# mux_lowside-V1_00.net
KiCad netlist of a schematic drawn in Altium Designer
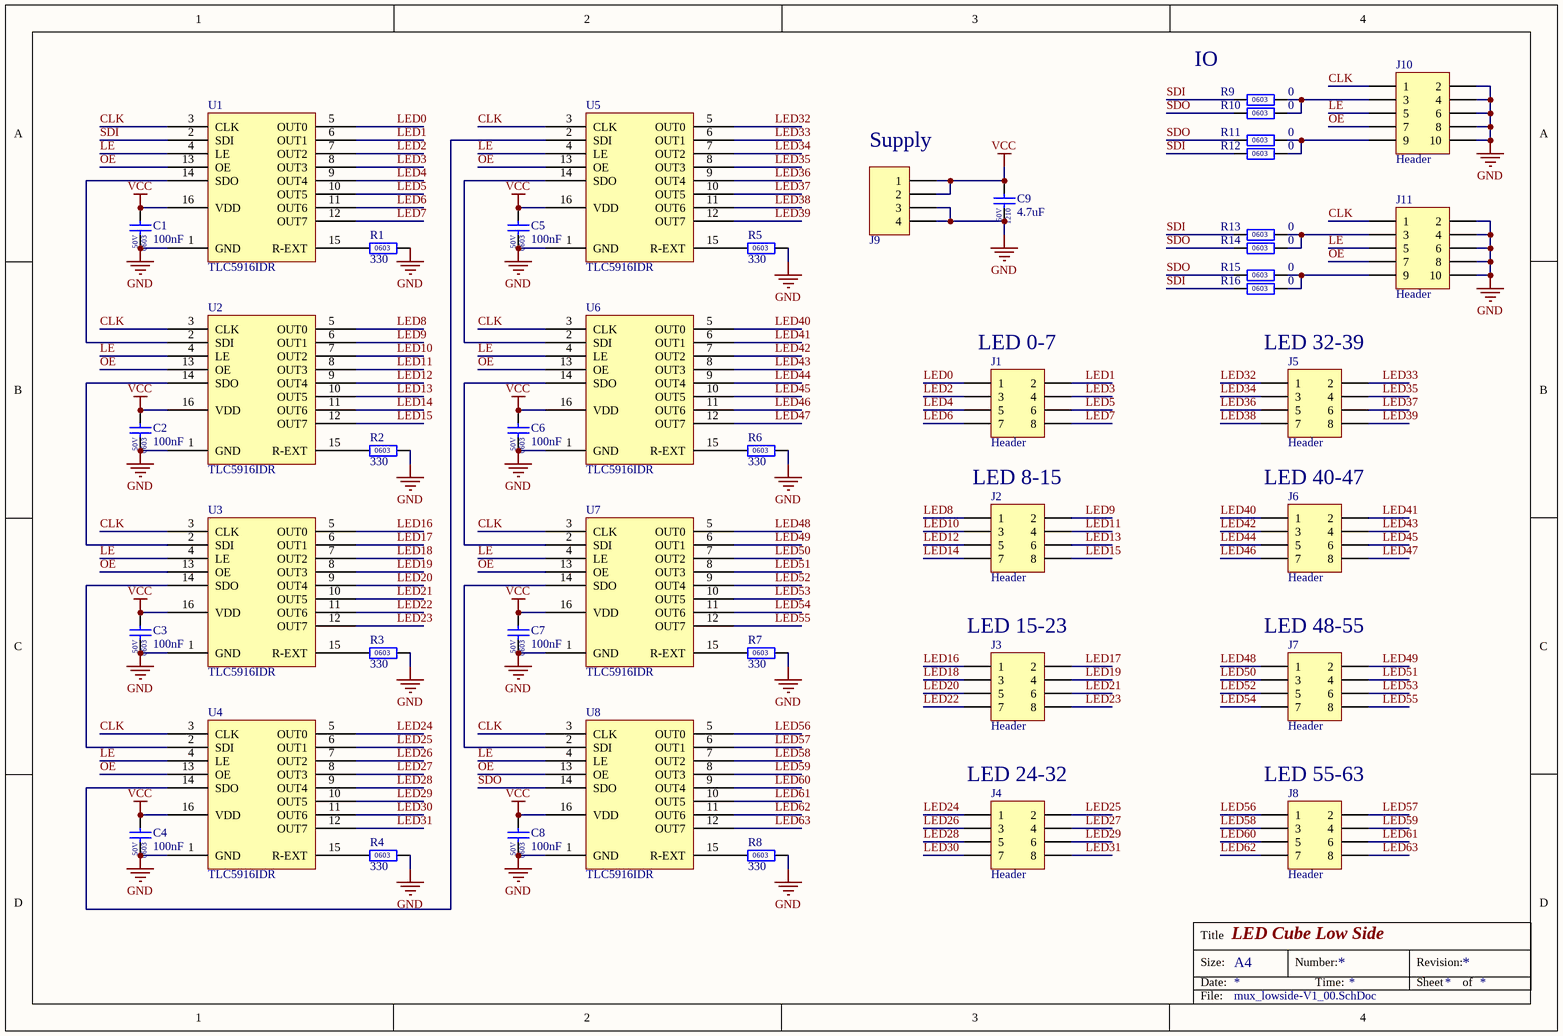
[diagram p0: mux_lowside-V1_00.SchDoc]

(export (version "E")
  (design (tool "Eeschema 10.0.6"))
  (components
    (comp (ref "C1")
      (value "Capacitor")
      (footprint "CAPC1608X10M_SILK")
      (description "CAP nF100   50V 0603 X7R 10%")
      (fields
        (field (name "MAX. VOLTAGE") "50V")
        (field (name "CAPACITY") "100nF")
        (field (name "PACKAGE") "0603")
        (field (name "PART NUMBER") "11026540")
        (field (name "TOLERANCE") "10%")
      )
      (libsource (lib "parts") (part "Capacitor"))
    )
    (comp (ref "C2")
      (value "Capacitor")
      (footprint "CAPC1608X10M_SILK")
      (description "CAP nF100   50V 0603 X7R 10%")
      (fields
        (field (name "MAX. VOLTAGE") "50V")
        (field (name "CAPACITY") "100nF")
        (field (name "PACKAGE") "0603")
        (field (name "PART NUMBER") "11026540")
        (field (name "TOLERANCE") "10%")
      )
      (libsource (lib "parts") (part "Capacitor"))
    )
    (comp (ref "C3")
      (value "Capacitor")
      (footprint "CAPC1608X10M_SILK")
      (description "CAP nF100   50V 0603 X7R 10%")
      (fields
        (field (name "MAX. VOLTAGE") "50V")
        (field (name "CAPACITY") "100nF")
        (field (name "PACKAGE") "0603")
        (field (name "PART NUMBER") "11026540")
        (field (name "TOLERANCE") "10%")
      )
      (libsource (lib "parts") (part "Capacitor"))
    )
    (comp (ref "C4")
      (value "Capacitor")
      (footprint "CAPC1608X10M_SILK")
      (description "CAP nF100   50V 0603 X7R 10%")
      (fields
        (field (name "MAX. VOLTAGE") "50V")
        (field (name "CAPACITY") "100nF")
        (field (name "PACKAGE") "0603")
        (field (name "PART NUMBER") "11026540")
        (field (name "TOLERANCE") "10%")
      )
      (libsource (lib "parts") (part "Capacitor"))
    )
    (comp (ref "C5")
      (value "Capacitor")
      (footprint "CAPC1608X10M_SILK")
      (description "CAP nF100   50V 0603 X7R 10%")
      (fields
        (field (name "MAX. VOLTAGE") "50V")
        (field (name "CAPACITY") "100nF")
        (field (name "PACKAGE") "0603")
        (field (name "PART NUMBER") "11026540")
        (field (name "TOLERANCE") "10%")
      )
      (libsource (lib "parts") (part "Capacitor"))
    )
    (comp (ref "C6")
      (value "Capacitor")
      (footprint "CAPC1608X10M_SILK")
      (description "CAP nF100   50V 0603 X7R 10%")
      (fields
        (field (name "MAX. VOLTAGE") "50V")
        (field (name "CAPACITY") "100nF")
        (field (name "PACKAGE") "0603")
        (field (name "PART NUMBER") "11026540")
        (field (name "TOLERANCE") "10%")
      )
      (libsource (lib "parts") (part "Capacitor"))
    )
    (comp (ref "C7")
      (value "Capacitor")
      (footprint "CAPC1608X10M_SILK")
      (description "CAP nF100   50V 0603 X7R 10%")
      (fields
        (field (name "MAX. VOLTAGE") "50V")
        (field (name "CAPACITY") "100nF")
        (field (name "PACKAGE") "0603")
        (field (name "PART NUMBER") "11026540")
        (field (name "TOLERANCE") "10%")
      )
      (libsource (lib "parts") (part "Capacitor"))
    )
    (comp (ref "C8")
      (value "Capacitor")
      (footprint "CAPC1608X10M_SILK")
      (description "CAP nF100   50V 0603 X7R 10%")
      (fields
        (field (name "MAX. VOLTAGE") "50V")
        (field (name "CAPACITY") "100nF")
        (field (name "PACKAGE") "0603")
        (field (name "PART NUMBER") "11026540")
        (field (name "TOLERANCE") "10%")
      )
      (libsource (lib "parts") (part "Capacitor"))
    )
    (comp (ref "C9")
      (value "Capacitor")
      (footprint "CAPC3225X17M_SILK")
      (description "CAP uF  4.7 50V 1210 X7R 10%")
      (fields
        (field (name "MAX. VOLTAGE") "50V")
        (field (name "CAPACITY") "4.7uF")
        (field (name "PACKAGE") "1210")
        (field (name "PART NUMBER") "10159411")
        (field (name "TOLERANCE") "10%")
      )
      (libsource (lib "parts") (part "Capacitor"))
    )
    (comp (ref "J1")
      (value "Header")
      (footprint "61200821621")
      (description "Box Header Male THT 2.54mm straight 8pos")
      (fields (field (name "PART NUMBER") "61200821621") (field (name "MANUFACTURER") "Wuerth"))
      (libsource (lib "parts") (part "Conn_02x04"))
    )
    (comp (ref "J2")
      (value "Header")
      (footprint "61200821621")
      (description "Box Header Male THT 2.54mm straight 8pos")
      (fields (field (name "PART NUMBER") "61200821621") (field (name "MANUFACTURER") "Wuerth"))
      (libsource (lib "parts") (part "Conn_02x04"))
    )
    (comp (ref "J3")
      (value "Header")
      (footprint "61200821621")
      (description "Box Header Male THT 2.54mm straight 8pos")
      (fields (field (name "PART NUMBER") "61200821621") (field (name "MANUFACTURER") "Wuerth"))
      (libsource (lib "parts") (part "Conn_02x04"))
    )
    (comp (ref "J4")
      (value "Header")
      (footprint "61200821621")
      (description "Box Header Male THT 2.54mm straight 8pos")
      (fields (field (name "PART NUMBER") "61200821621") (field (name "MANUFACTURER") "Wuerth"))
      (libsource (lib "parts") (part "Conn_02x04"))
    )
    (comp (ref "J5")
      (value "Header")
      (footprint "61200821621")
      (description "Box Header Male THT 2.54mm straight 8pos")
      (fields (field (name "PART NUMBER") "61200821621") (field (name "MANUFACTURER") "Wuerth"))
      (libsource (lib "parts") (part "Conn_02x04"))
    )
    (comp (ref "J6")
      (value "Header")
      (footprint "61200821621")
      (description "Box Header Male THT 2.54mm straight 8pos")
      (fields (field (name "PART NUMBER") "61200821621") (field (name "MANUFACTURER") "Wuerth"))
      (libsource (lib "parts") (part "Conn_02x04"))
    )
    (comp (ref "J7")
      (value "Header")
      (footprint "61200821621")
      (description "Box Header Male THT 2.54mm straight 8pos")
      (fields (field (name "PART NUMBER") "61200821621") (field (name "MANUFACTURER") "Wuerth"))
      (libsource (lib "parts") (part "Conn_02x04"))
    )
    (comp (ref "J8")
      (value "Header")
      (footprint "61200821621")
      (description "Box Header Male THT 2.54mm straight 8pos")
      (fields (field (name "PART NUMBER") "61200821621") (field (name "MANUFACTURER") "Wuerth"))
      (libsource (lib "parts") (part "Conn_02x04"))
    )
    (comp (ref "J9")
      (value "MSTBA 2,5/ 4-G-5,08")
      (footprint "1757268")
      (description "PCB Header, 2.54mm, angled, 4pol")
      (fields (field (name "MANUFACTURER") "Phoenix Contact"))
      (libsource (lib "parts") (part "Conn_01x04"))
    )
    (comp (ref "J10")
      (value "Header")
      (footprint "61201021721")
      (description "Box Header Male THT 2.54mm angled 10pos")
      (fields (field (name "PART NUMBER") "61201021721") (field (name "MANUFACTURER") "Wuerth"))
      (libsource (lib "parts") (part "Conn_02x05"))
    )
    (comp (ref "J11")
      (value "Header")
      (footprint "61201021721")
      (description "Box Header Male THT 2.54mm angled 10pos")
      (fields (field (name "PART NUMBER") "61201021721") (field (name "MANUFACTURER") "Wuerth"))
      (libsource (lib "parts") (part "Conn_02x05"))
    )
    (comp (ref "R1")
      (value "330")
      (footprint "RESC1608X06M_SILK")
      (description "Resistor 330 1% 0603")
      (fields
        (field (name "PACKAGE") "0603")
        (field (name "PART NUMBER") "RES_330_0603")
        (field (name "TOLERANCE") "1%")
      )
      (libsource (lib "parts") (part "resistor"))
    )
    (comp (ref "R2")
      (value "330")
      (footprint "RESC1608X06M_SILK")
      (description "Resistor 330 1% 0603")
      (fields
        (field (name "PACKAGE") "0603")
        (field (name "PART NUMBER") "RES_330_0603")
        (field (name "TOLERANCE") "1%")
      )
      (libsource (lib "parts") (part "resistor"))
    )
    (comp (ref "R3")
      (value "330")
      (footprint "RESC1608X06M_SILK")
      (description "Resistor 330 1% 0603")
      (fields
        (field (name "PACKAGE") "0603")
        (field (name "PART NUMBER") "RES_330_0603")
        (field (name "TOLERANCE") "1%")
      )
      (libsource (lib "parts") (part "resistor"))
    )
    (comp (ref "R4")
      (value "330")
      (footprint "RESC1608X06M_SILK")
      (description "Resistor 330 1% 0603")
      (fields
        (field (name "PACKAGE") "0603")
        (field (name "PART NUMBER") "RES_330_0603")
        (field (name "TOLERANCE") "1%")
      )
      (libsource (lib "parts") (part "resistor"))
    )
    (comp (ref "R5")
      (value "330")
      (footprint "RESC1608X06M_SILK")
      (description "Resistor 330 1% 0603")
      (fields
        (field (name "PACKAGE") "0603")
        (field (name "PART NUMBER") "RES_330_0603")
        (field (name "TOLERANCE") "1%")
      )
      (libsource (lib "parts") (part "resistor"))
    )
    (comp (ref "R6")
      (value "330")
      (footprint "RESC1608X06M_SILK")
      (description "Resistor 330 1% 0603")
      (fields
        (field (name "PACKAGE") "0603")
        (field (name "PART NUMBER") "RES_330_0603")
        (field (name "TOLERANCE") "1%")
      )
      (libsource (lib "parts") (part "resistor"))
    )
    (comp (ref "R7")
      (value "330")
      (footprint "RESC1608X06M_SILK")
      (description "Resistor 330 1% 0603")
      (fields
        (field (name "PACKAGE") "0603")
        (field (name "PART NUMBER") "RES_330_0603")
        (field (name "TOLERANCE") "1%")
      )
      (libsource (lib "parts") (part "resistor"))
    )
    (comp (ref "R8")
      (value "330")
      (footprint "RESC1608X06M_SILK")
      (description "Resistor 330 1% 0603")
      (fields
        (field (name "PACKAGE") "0603")
        (field (name "PART NUMBER") "RES_330_0603")
        (field (name "TOLERANCE") "1%")
      )
      (libsource (lib "parts") (part "resistor"))
    )
    (comp (ref "R9")
      (value "0")
      (footprint "RESC1608X06M_SILK")
      (description "Resistor 0 1% 0603")
      (fields
        (field (name "PACKAGE") "0603")
        (field (name "PART NUMBER") "RES_0_0603")
        (field (name "TOLERANCE") "1%")
      )
      (libsource (lib "parts") (part "resistor"))
    )
    (comp (ref "R10")
      (value "0")
      (footprint "RESC1608X06M_SILK")
      (description "Resistor 0 1% 0603")
      (fields
        (field (name "PACKAGE") "0603")
        (field (name "PART NUMBER") "RES_0_0603")
        (field (name "TOLERANCE") "1%")
      )
      (libsource (lib "parts") (part "resistor"))
    )
    (comp (ref "R11")
      (value "0")
      (footprint "RESC1608X06M_SILK")
      (description "Resistor 0 1% 0603")
      (fields
        (field (name "PACKAGE") "0603")
        (field (name "PART NUMBER") "RES_0_0603")
        (field (name "TOLERANCE") "1%")
      )
      (libsource (lib "parts") (part "resistor"))
    )
    (comp (ref "R12")
      (value "0")
      (footprint "RESC1608X06M_SILK")
      (description "Resistor 0 1% 0603")
      (fields
        (field (name "PACKAGE") "0603")
        (field (name "PART NUMBER") "RES_0_0603")
        (field (name "TOLERANCE") "1%")
      )
      (libsource (lib "parts") (part "resistor"))
    )
    (comp (ref "R13")
      (value "0")
      (footprint "RESC1608X06M_SILK")
      (description "Resistor 0 1% 0603")
      (fields
        (field (name "PACKAGE") "0603")
        (field (name "PART NUMBER") "RES_0_0603")
        (field (name "TOLERANCE") "1%")
      )
      (libsource (lib "parts") (part "resistor"))
    )
    (comp (ref "R14")
      (value "0")
      (footprint "RESC1608X06M_SILK")
      (description "Resistor 0 1% 0603")
      (fields
        (field (name "PACKAGE") "0603")
        (field (name "PART NUMBER") "RES_0_0603")
        (field (name "TOLERANCE") "1%")
      )
      (libsource (lib "parts") (part "resistor"))
    )
    (comp (ref "R15")
      (value "0")
      (footprint "RESC1608X06M_SILK")
      (description "Resistor 0 1% 0603")
      (fields
        (field (name "PACKAGE") "0603")
        (field (name "PART NUMBER") "RES_0_0603")
        (field (name "TOLERANCE") "1%")
      )
      (libsource (lib "parts") (part "resistor"))
    )
    (comp (ref "R16")
      (value "0")
      (footprint "RESC1608X06M_SILK")
      (description "Resistor 0 1% 0603")
      (fields
        (field (name "PACKAGE") "0603")
        (field (name "PART NUMBER") "RES_0_0603")
        (field (name "TOLERANCE") "1%")
      )
      (libsource (lib "parts") (part "resistor"))
    )
    (comp (ref "U1")
      (value "TLC5916IDR")
      (footprint "SOIC127P600X175-16M")
      (description "TLC5916IDR 8 channel LED Const. Current Sink Driver")
      (fields (field (name "MANUFACTURER") "Texas Instruments"))
      (libsource (lib "parts") (part "TLC5916"))
    )
    (comp (ref "U2")
      (value "TLC5916IDR")
      (footprint "SOIC127P600X175-16M")
      (description "TLC5916IDR 8 channel LED Const. Current Sink Driver")
      (fields (field (name "MANUFACTURER") "Texas Instruments"))
      (libsource (lib "parts") (part "TLC5916"))
    )
    (comp (ref "U3")
      (value "TLC5916IDR")
      (footprint "SOIC127P600X175-16M")
      (description "TLC5916IDR 8 channel LED Const. Current Sink Driver")
      (fields (field (name "MANUFACTURER") "Texas Instruments"))
      (libsource (lib "parts") (part "TLC5916"))
    )
    (comp (ref "U4")
      (value "TLC5916IDR")
      (footprint "SOIC127P600X175-16M")
      (description "TLC5916IDR 8 channel LED Const. Current Sink Driver")
      (fields (field (name "MANUFACTURER") "Texas Instruments"))
      (libsource (lib "parts") (part "TLC5916"))
    )
    (comp (ref "U5")
      (value "TLC5916IDR")
      (footprint "SOIC127P600X175-16M")
      (description "TLC5916IDR 8 channel LED Const. Current Sink Driver")
      (fields (field (name "MANUFACTURER") "Texas Instruments"))
      (libsource (lib "parts") (part "TLC5916"))
    )
    (comp (ref "U6")
      (value "TLC5916IDR")
      (footprint "SOIC127P600X175-16M")
      (description "TLC5916IDR 8 channel LED Const. Current Sink Driver")
      (fields (field (name "MANUFACTURER") "Texas Instruments"))
      (libsource (lib "parts") (part "TLC5916"))
    )
    (comp (ref "U7")
      (value "TLC5916IDR")
      (footprint "SOIC127P600X175-16M")
      (description "TLC5916IDR 8 channel LED Const. Current Sink Driver")
      (fields (field (name "MANUFACTURER") "Texas Instruments"))
      (libsource (lib "parts") (part "TLC5916"))
    )
    (comp (ref "U8")
      (value "TLC5916IDR")
      (footprint "SOIC127P600X175-16M")
      (description "TLC5916IDR 8 channel LED Const. Current Sink Driver")
      (fields (field (name "MANUFACTURER") "Texas Instruments"))
      (libsource (lib "parts") (part "TLC5916"))
    )
  )
  (nets
    (net (code "1") (name "/CLK") (class "Default")
      (node (ref "J10") (pin "1") (pinfunction "1_1") (pintype "passive"))
      (node (ref "J11") (pin "1") (pinfunction "1_1") (pintype "passive"))
      (node (ref "U1") (pin "3") (pinfunction "CLK_3") (pintype "passive"))
      (node (ref "U2") (pin "3") (pinfunction "CLK_3") (pintype "passive"))
      (node (ref "U3") (pin "3") (pinfunction "CLK_3") (pintype "passive"))
      (node (ref "U4") (pin "3") (pinfunction "CLK_3") (pintype "passive"))
      (node (ref "U5") (pin "3") (pinfunction "CLK_3") (pintype "passive"))
      (node (ref "U6") (pin "3") (pinfunction "CLK_3") (pintype "passive"))
      (node (ref "U7") (pin "3") (pinfunction "CLK_3") (pintype "passive"))
      (node (ref "U8") (pin "3") (pinfunction "CLK_3") (pintype "passive"))
    )
    (net (code "2") (name "/LE") (class "Default")
      (node (ref "J10") (pin "5") (pinfunction "5_5") (pintype "passive"))
      (node (ref "J11") (pin "5") (pinfunction "5_5") (pintype "passive"))
      (node (ref "U1") (pin "4") (pinfunction "LE_4") (pintype "passive"))
      (node (ref "U2") (pin "4") (pinfunction "LE_4") (pintype "passive"))
      (node (ref "U3") (pin "4") (pinfunction "LE_4") (pintype "passive"))
      (node (ref "U4") (pin "4") (pinfunction "LE_4") (pintype "passive"))
      (node (ref "U5") (pin "4") (pinfunction "LE_4") (pintype "passive"))
      (node (ref "U6") (pin "4") (pinfunction "LE_4") (pintype "passive"))
      (node (ref "U7") (pin "4") (pinfunction "LE_4") (pintype "passive"))
      (node (ref "U8") (pin "4") (pinfunction "LE_4") (pintype "passive"))
    )
    (net (code "3") (name "/LED0") (class "Default")
      (node (ref "J1") (pin "1") (pinfunction "1_1") (pintype "passive"))
      (node (ref "U1") (pin "5") (pinfunction "OUT0_5") (pintype "passive"))
    )
    (net (code "4") (name "/LED1") (class "Default")
      (node (ref "J1") (pin "2") (pinfunction "2_2") (pintype "passive"))
      (node (ref "U1") (pin "6") (pinfunction "OUT1_6") (pintype "passive"))
    )
    (net (code "5") (name "/LED2") (class "Default")
      (node (ref "J1") (pin "3") (pinfunction "3_3") (pintype "passive"))
      (node (ref "U1") (pin "7") (pinfunction "OUT2_7") (pintype "passive"))
    )
    (net (code "6") (name "/LED3") (class "Default")
      (node (ref "J1") (pin "4") (pinfunction "4_4") (pintype "passive"))
      (node (ref "U1") (pin "8") (pinfunction "OUT3_8") (pintype "passive"))
    )
    (net (code "7") (name "/LED4") (class "Default")
      (node (ref "J1") (pin "5") (pinfunction "5_5") (pintype "passive"))
      (node (ref "U1") (pin "9") (pinfunction "OUT4_9") (pintype "passive"))
    )
    (net (code "8") (name "/LED5") (class "Default")
      (node (ref "J1") (pin "6") (pinfunction "6_6") (pintype "passive"))
      (node (ref "U1") (pin "10") (pinfunction "OUT5_10") (pintype "passive"))
    )
    (net (code "9") (name "/LED6") (class "Default")
      (node (ref "J1") (pin "7") (pinfunction "7_7") (pintype "passive"))
      (node (ref "U1") (pin "11") (pinfunction "OUT6_11") (pintype "passive"))
    )
    (net (code "10") (name "/LED7") (class "Default")
      (node (ref "J1") (pin "8") (pinfunction "8_8") (pintype "passive"))
      (node (ref "U1") (pin "12") (pinfunction "OUT7_12") (pintype "passive"))
    )
    (net (code "11") (name "/LED8") (class "Default")
      (node (ref "J2") (pin "1") (pinfunction "1_1") (pintype "passive"))
      (node (ref "U2") (pin "5") (pinfunction "OUT0_5") (pintype "passive"))
    )
    (net (code "12") (name "/LED9") (class "Default")
      (node (ref "J2") (pin "2") (pinfunction "2_2") (pintype "passive"))
      (node (ref "U2") (pin "6") (pinfunction "OUT1_6") (pintype "passive"))
    )
    (net (code "13") (name "/LED10") (class "Default")
      (node (ref "J2") (pin "3") (pinfunction "3_3") (pintype "passive"))
      (node (ref "U2") (pin "7") (pinfunction "OUT2_7") (pintype "passive"))
    )
    (net (code "14") (name "/LED11") (class "Default")
      (node (ref "J2") (pin "4") (pinfunction "4_4") (pintype "passive"))
      (node (ref "U2") (pin "8") (pinfunction "OUT3_8") (pintype "passive"))
    )
    (net (code "15") (name "/LED12") (class "Default")
      (node (ref "J2") (pin "5") (pinfunction "5_5") (pintype "passive"))
      (node (ref "U2") (pin "9") (pinfunction "OUT4_9") (pintype "passive"))
    )
    (net (code "16") (name "/LED13") (class "Default")
      (node (ref "J2") (pin "6") (pinfunction "6_6") (pintype "passive"))
      (node (ref "U2") (pin "10") (pinfunction "OUT5_10") (pintype "passive"))
    )
    (net (code "17") (name "/LED14") (class "Default")
      (node (ref "J2") (pin "7") (pinfunction "7_7") (pintype "passive"))
      (node (ref "U2") (pin "11") (pinfunction "OUT6_11") (pintype "passive"))
    )
    (net (code "18") (name "/LED15") (class "Default")
      (node (ref "J2") (pin "8") (pinfunction "8_8") (pintype "passive"))
      (node (ref "U2") (pin "12") (pinfunction "OUT7_12") (pintype "passive"))
    )
    (net (code "19") (name "/LED16") (class "Default")
      (node (ref "J3") (pin "1") (pinfunction "1_1") (pintype "passive"))
      (node (ref "U3") (pin "5") (pinfunction "OUT0_5") (pintype "passive"))
    )
    (net (code "20") (name "/LED17") (class "Default")
      (node (ref "J3") (pin "2") (pinfunction "2_2") (pintype "passive"))
      (node (ref "U3") (pin "6") (pinfunction "OUT1_6") (pintype "passive"))
    )
    (net (code "21") (name "/LED18") (class "Default")
      (node (ref "J3") (pin "3") (pinfunction "3_3") (pintype "passive"))
      (node (ref "U3") (pin "7") (pinfunction "OUT2_7") (pintype "passive"))
    )
    (net (code "22") (name "/LED19") (class "Default")
      (node (ref "J3") (pin "4") (pinfunction "4_4") (pintype "passive"))
      (node (ref "U3") (pin "8") (pinfunction "OUT3_8") (pintype "passive"))
    )
    (net (code "23") (name "/LED20") (class "Default")
      (node (ref "J3") (pin "5") (pinfunction "5_5") (pintype "passive"))
      (node (ref "U3") (pin "9") (pinfunction "OUT4_9") (pintype "passive"))
    )
    (net (code "24") (name "/LED21") (class "Default")
      (node (ref "J3") (pin "6") (pinfunction "6_6") (pintype "passive"))
      (node (ref "U3") (pin "10") (pinfunction "OUT5_10") (pintype "passive"))
    )
    (net (code "25") (name "/LED22") (class "Default")
      (node (ref "J3") (pin "7") (pinfunction "7_7") (pintype "passive"))
      (node (ref "U3") (pin "11") (pinfunction "OUT6_11") (pintype "passive"))
    )
    (net (code "26") (name "/LED23") (class "Default")
      (node (ref "J3") (pin "8") (pinfunction "8_8") (pintype "passive"))
      (node (ref "U3") (pin "12") (pinfunction "OUT7_12") (pintype "passive"))
    )
    (net (code "27") (name "/LED24") (class "Default")
      (node (ref "J4") (pin "1") (pinfunction "1_1") (pintype "passive"))
      (node (ref "U4") (pin "5") (pinfunction "OUT0_5") (pintype "passive"))
    )
    (net (code "28") (name "/LED25") (class "Default")
      (node (ref "J4") (pin "2") (pinfunction "2_2") (pintype "passive"))
      (node (ref "U4") (pin "6") (pinfunction "OUT1_6") (pintype "passive"))
    )
    (net (code "29") (name "/LED26") (class "Default")
      (node (ref "J4") (pin "3") (pinfunction "3_3") (pintype "passive"))
      (node (ref "U4") (pin "7") (pinfunction "OUT2_7") (pintype "passive"))
    )
    (net (code "30") (name "/LED27") (class "Default")
      (node (ref "J4") (pin "4") (pinfunction "4_4") (pintype "passive"))
      (node (ref "U4") (pin "8") (pinfunction "OUT3_8") (pintype "passive"))
    )
    (net (code "31") (name "/LED28") (class "Default")
      (node (ref "J4") (pin "5") (pinfunction "5_5") (pintype "passive"))
      (node (ref "U4") (pin "9") (pinfunction "OUT4_9") (pintype "passive"))
    )
    (net (code "32") (name "/LED29") (class "Default")
      (node (ref "J4") (pin "6") (pinfunction "6_6") (pintype "passive"))
      (node (ref "U4") (pin "10") (pinfunction "OUT5_10") (pintype "passive"))
    )
    (net (code "33") (name "/LED30") (class "Default")
      (node (ref "J4") (pin "7") (pinfunction "7_7") (pintype "passive"))
      (node (ref "U4") (pin "11") (pinfunction "OUT6_11") (pintype "passive"))
    )
    (net (code "34") (name "/LED31") (class "Default")
      (node (ref "J4") (pin "8") (pinfunction "8_8") (pintype "passive"))
      (node (ref "U4") (pin "12") (pinfunction "OUT7_12") (pintype "passive"))
    )
    (net (code "35") (name "/LED32") (class "Default")
      (node (ref "J5") (pin "1") (pinfunction "1_1") (pintype "passive"))
      (node (ref "U5") (pin "5") (pinfunction "OUT0_5") (pintype "passive"))
    )
    (net (code "36") (name "/LED33") (class "Default")
      (node (ref "J5") (pin "2") (pinfunction "2_2") (pintype "passive"))
      (node (ref "U5") (pin "6") (pinfunction "OUT1_6") (pintype "passive"))
    )
    (net (code "37") (name "/LED34") (class "Default")
      (node (ref "J5") (pin "3") (pinfunction "3_3") (pintype "passive"))
      (node (ref "U5") (pin "7") (pinfunction "OUT2_7") (pintype "passive"))
    )
    (net (code "38") (name "/LED35") (class "Default")
      (node (ref "J5") (pin "4") (pinfunction "4_4") (pintype "passive"))
      (node (ref "U5") (pin "8") (pinfunction "OUT3_8") (pintype "passive"))
    )
    (net (code "39") (name "/LED36") (class "Default")
      (node (ref "J5") (pin "5") (pinfunction "5_5") (pintype "passive"))
      (node (ref "U5") (pin "9") (pinfunction "OUT4_9") (pintype "passive"))
    )
    (net (code "40") (name "/LED37") (class "Default")
      (node (ref "J5") (pin "6") (pinfunction "6_6") (pintype "passive"))
      (node (ref "U5") (pin "10") (pinfunction "OUT5_10") (pintype "passive"))
    )
    (net (code "41") (name "/LED38") (class "Default")
      (node (ref "J5") (pin "7") (pinfunction "7_7") (pintype "passive"))
      (node (ref "U5") (pin "11") (pinfunction "OUT6_11") (pintype "passive"))
    )
    (net (code "42") (name "/LED39") (class "Default")
      (node (ref "J5") (pin "8") (pinfunction "8_8") (pintype "passive"))
      (node (ref "U5") (pin "12") (pinfunction "OUT7_12") (pintype "passive"))
    )
    (net (code "43") (name "/LED40") (class "Default")
      (node (ref "J6") (pin "1") (pinfunction "1_1") (pintype "passive"))
      (node (ref "U6") (pin "5") (pinfunction "OUT0_5") (pintype "passive"))
    )
    (net (code "44") (name "/LED41") (class "Default")
      (node (ref "J6") (pin "2") (pinfunction "2_2") (pintype "passive"))
      (node (ref "U6") (pin "6") (pinfunction "OUT1_6") (pintype "passive"))
    )
    (net (code "45") (name "/LED42") (class "Default")
      (node (ref "J6") (pin "3") (pinfunction "3_3") (pintype "passive"))
      (node (ref "U6") (pin "7") (pinfunction "OUT2_7") (pintype "passive"))
    )
    (net (code "46") (name "/LED43") (class "Default")
      (node (ref "J6") (pin "4") (pinfunction "4_4") (pintype "passive"))
      (node (ref "U6") (pin "8") (pinfunction "OUT3_8") (pintype "passive"))
    )
    (net (code "47") (name "/LED44") (class "Default")
      (node (ref "J6") (pin "5") (pinfunction "5_5") (pintype "passive"))
      (node (ref "U6") (pin "9") (pinfunction "OUT4_9") (pintype "passive"))
    )
    (net (code "48") (name "/LED45") (class "Default")
      (node (ref "J6") (pin "6") (pinfunction "6_6") (pintype "passive"))
      (node (ref "U6") (pin "10") (pinfunction "OUT5_10") (pintype "passive"))
    )
    (net (code "49") (name "/LED46") (class "Default")
      (node (ref "J6") (pin "7") (pinfunction "7_7") (pintype "passive"))
      (node (ref "U6") (pin "11") (pinfunction "OUT6_11") (pintype "passive"))
    )
    (net (code "50") (name "/LED47") (class "Default")
      (node (ref "J6") (pin "8") (pinfunction "8_8") (pintype "passive"))
      (node (ref "U6") (pin "12") (pinfunction "OUT7_12") (pintype "passive"))
    )
    (net (code "51") (name "/LED48") (class "Default")
      (node (ref "J7") (pin "1") (pinfunction "1_1") (pintype "passive"))
      (node (ref "U7") (pin "5") (pinfunction "OUT0_5") (pintype "passive"))
    )
    (net (code "52") (name "/LED49") (class "Default")
      (node (ref "J7") (pin "2") (pinfunction "2_2") (pintype "passive"))
      (node (ref "U7") (pin "6") (pinfunction "OUT1_6") (pintype "passive"))
    )
    (net (code "53") (name "/LED50") (class "Default")
      (node (ref "J7") (pin "3") (pinfunction "3_3") (pintype "passive"))
      (node (ref "U7") (pin "7") (pinfunction "OUT2_7") (pintype "passive"))
    )
    (net (code "54") (name "/LED51") (class "Default")
      (node (ref "J7") (pin "4") (pinfunction "4_4") (pintype "passive"))
      (node (ref "U7") (pin "8") (pinfunction "OUT3_8") (pintype "passive"))
    )
    (net (code "55") (name "/LED52") (class "Default")
      (node (ref "J7") (pin "5") (pinfunction "5_5") (pintype "passive"))
      (node (ref "U7") (pin "9") (pinfunction "OUT4_9") (pintype "passive"))
    )
    (net (code "56") (name "/LED53") (class "Default")
      (node (ref "J7") (pin "6") (pinfunction "6_6") (pintype "passive"))
      (node (ref "U7") (pin "10") (pinfunction "OUT5_10") (pintype "passive"))
    )
    (net (code "57") (name "/LED54") (class "Default")
      (node (ref "J7") (pin "7") (pinfunction "7_7") (pintype "passive"))
      (node (ref "U7") (pin "11") (pinfunction "OUT6_11") (pintype "passive"))
    )
    (net (code "58") (name "/LED55") (class "Default")
      (node (ref "J7") (pin "8") (pinfunction "8_8") (pintype "passive"))
      (node (ref "U7") (pin "12") (pinfunction "OUT7_12") (pintype "passive"))
    )
    (net (code "59") (name "/LED56") (class "Default")
      (node (ref "J8") (pin "1") (pinfunction "1_1") (pintype "passive"))
      (node (ref "U8") (pin "5") (pinfunction "OUT0_5") (pintype "passive"))
    )
    (net (code "60") (name "/LED57") (class "Default")
      (node (ref "J8") (pin "2") (pinfunction "2_2") (pintype "passive"))
      (node (ref "U8") (pin "6") (pinfunction "OUT1_6") (pintype "passive"))
    )
    (net (code "61") (name "/LED58") (class "Default")
      (node (ref "J8") (pin "3") (pinfunction "3_3") (pintype "passive"))
      (node (ref "U8") (pin "7") (pinfunction "OUT2_7") (pintype "passive"))
    )
    (net (code "62") (name "/LED59") (class "Default")
      (node (ref "J8") (pin "4") (pinfunction "4_4") (pintype "passive"))
      (node (ref "U8") (pin "8") (pinfunction "OUT3_8") (pintype "passive"))
    )
    (net (code "63") (name "/LED60") (class "Default")
      (node (ref "J8") (pin "5") (pinfunction "5_5") (pintype "passive"))
      (node (ref "U8") (pin "9") (pinfunction "OUT4_9") (pintype "passive"))
    )
    (net (code "64") (name "/LED61") (class "Default")
      (node (ref "J8") (pin "6") (pinfunction "6_6") (pintype "passive"))
      (node (ref "U8") (pin "10") (pinfunction "OUT5_10") (pintype "passive"))
    )
    (net (code "65") (name "/LED62") (class "Default")
      (node (ref "J8") (pin "7") (pinfunction "7_7") (pintype "passive"))
      (node (ref "U8") (pin "11") (pinfunction "OUT6_11") (pintype "passive"))
    )
    (net (code "66") (name "/LED63") (class "Default")
      (node (ref "J8") (pin "8") (pinfunction "8_8") (pintype "passive"))
      (node (ref "U8") (pin "12") (pinfunction "OUT7_12") (pintype "passive"))
    )
    (net (code "67") (name "/OE") (class "Default")
      (node (ref "J10") (pin "7") (pinfunction "7_7") (pintype "passive"))
      (node (ref "J11") (pin "7") (pinfunction "7_7") (pintype "passive"))
      (node (ref "U1") (pin "13") (pinfunction "OE_13") (pintype "passive"))
      (node (ref "U2") (pin "13") (pinfunction "OE_13") (pintype "passive"))
      (node (ref "U3") (pin "13") (pinfunction "OE_13") (pintype "passive"))
      (node (ref "U4") (pin "13") (pinfunction "OE_13") (pintype "passive"))
      (node (ref "U5") (pin "13") (pinfunction "OE_13") (pintype "passive"))
      (node (ref "U6") (pin "13") (pinfunction "OE_13") (pintype "passive"))
      (node (ref "U7") (pin "13") (pinfunction "OE_13") (pintype "passive"))
      (node (ref "U8") (pin "13") (pinfunction "OE_13") (pintype "passive"))
    )
    (net (code "68") (name "/SDI") (class "Default")
      (node (ref "R12") (pin "1") (pinfunction "1_1") (pintype "passive"))
      (node (ref "R13") (pin "1") (pinfunction "1_1") (pintype "passive"))
      (node (ref "R16") (pin "1") (pinfunction "1_1") (pintype "passive"))
      (node (ref "R9") (pin "1") (pinfunction "1_1") (pintype "passive"))
      (node (ref "U1") (pin "2") (pinfunction "SDI_2") (pintype "passive"))
    )
    (net (code "69") (name "/SDO") (class "Default")
      (node (ref "R10") (pin "1") (pinfunction "1_1") (pintype "passive"))
      (node (ref "R11") (pin "1") (pinfunction "1_1") (pintype "passive"))
      (node (ref "R14") (pin "1") (pinfunction "1_1") (pintype "passive"))
      (node (ref "R15") (pin "1") (pinfunction "1_1") (pintype "passive"))
      (node (ref "U8") (pin "14") (pinfunction "SDO_14") (pintype "passive"))
    )
    (net (code "70") (name "GND") (class "Default")
      (node (ref "C1") (pin "1") (pinfunction "1_1") (pintype "passive"))
      (node (ref "C2") (pin "1") (pinfunction "1_1") (pintype "passive"))
      (node (ref "C3") (pin "1") (pinfunction "1_1") (pintype "passive"))
      (node (ref "C4") (pin "1") (pinfunction "1_1") (pintype "passive"))
      (node (ref "C5") (pin "1") (pinfunction "1_1") (pintype "passive"))
      (node (ref "C6") (pin "1") (pinfunction "1_1") (pintype "passive"))
      (node (ref "C7") (pin "1") (pinfunction "1_1") (pintype "passive"))
      (node (ref "C8") (pin "1") (pinfunction "1_1") (pintype "passive"))
      (node (ref "C9") (pin "1") (pinfunction "1_1") (pintype "passive"))
      (node (ref "J10") (pin "10") (pinfunction "10_10") (pintype "passive"))
      (node (ref "J10") (pin "2") (pinfunction "2_2") (pintype "passive"))
      (node (ref "J10") (pin "4") (pinfunction "4_4") (pintype "passive"))
      (node (ref "J10") (pin "6") (pinfunction "6_6") (pintype "passive"))
      (node (ref "J10") (pin "8") (pinfunction "8_8") (pintype "passive"))
      (node (ref "J11") (pin "10") (pinfunction "10_10") (pintype "passive"))
      (node (ref "J11") (pin "2") (pinfunction "2_2") (pintype "passive"))
      (node (ref "J11") (pin "4") (pinfunction "4_4") (pintype "passive"))
      (node (ref "J11") (pin "6") (pinfunction "6_6") (pintype "passive"))
      (node (ref "J11") (pin "8") (pinfunction "8_8") (pintype "passive"))
      (node (ref "J9") (pin "3") (pinfunction "3_3") (pintype "passive"))
      (node (ref "J9") (pin "4") (pinfunction "4_4") (pintype "passive"))
      (node (ref "R1") (pin "2") (pinfunction "2_2") (pintype "passive"))
      (node (ref "R2") (pin "2") (pinfunction "2_2") (pintype "passive"))
      (node (ref "R3") (pin "2") (pinfunction "2_2") (pintype "passive"))
      (node (ref "R4") (pin "2") (pinfunction "2_2") (pintype "passive"))
      (node (ref "R5") (pin "2") (pinfunction "2_2") (pintype "passive"))
      (node (ref "R6") (pin "2") (pinfunction "2_2") (pintype "passive"))
      (node (ref "R7") (pin "2") (pinfunction "2_2") (pintype "passive"))
      (node (ref "R8") (pin "2") (pinfunction "2_2") (pintype "passive"))
      (node (ref "U1") (pin "1") (pinfunction "GND_1") (pintype "passive"))
      (node (ref "U2") (pin "1") (pinfunction "GND_1") (pintype "passive"))
      (node (ref "U3") (pin "1") (pinfunction "GND_1") (pintype "passive"))
      (node (ref "U4") (pin "1") (pinfunction "GND_1") (pintype "passive"))
      (node (ref "U5") (pin "1") (pinfunction "GND_1") (pintype "passive"))
      (node (ref "U6") (pin "1") (pinfunction "GND_1") (pintype "passive"))
      (node (ref "U7") (pin "1") (pinfunction "GND_1") (pintype "passive"))
      (node (ref "U8") (pin "1") (pinfunction "GND_1") (pintype "passive"))
    )
    (net (code "71") (name "Net-(J10-Pad3)") (class "Default")
      (node (ref "J10") (pin "3") (pinfunction "3_3") (pintype "passive"))
      (node (ref "R10") (pin "2") (pinfunction "2_2") (pintype "passive"))
      (node (ref "R9") (pin "2") (pinfunction "2_2") (pintype "passive"))
    )
    (net (code "72") (name "Net-(J10-Pad9)") (class "Default")
      (node (ref "J10") (pin "9") (pinfunction "9_9") (pintype "passive"))
      (node (ref "R11") (pin "2") (pinfunction "2_2") (pintype "passive"))
      (node (ref "R12") (pin "2") (pinfunction "2_2") (pintype "passive"))
    )
    (net (code "73") (name "Net-(J11-Pad3)") (class "Default")
      (node (ref "J11") (pin "3") (pinfunction "3_3") (pintype "passive"))
      (node (ref "R13") (pin "2") (pinfunction "2_2") (pintype "passive"))
      (node (ref "R14") (pin "2") (pinfunction "2_2") (pintype "passive"))
    )
    (net (code "74") (name "Net-(J11-Pad9)") (class "Default")
      (node (ref "J11") (pin "9") (pinfunction "9_9") (pintype "passive"))
      (node (ref "R15") (pin "2") (pinfunction "2_2") (pintype "passive"))
      (node (ref "R16") (pin "2") (pinfunction "2_2") (pintype "passive"))
    )
    (net (code "75") (name "Net-(U1-R-EXT)") (class "Default")
      (node (ref "R1") (pin "1") (pinfunction "1_1") (pintype "passive"))
      (node (ref "U1") (pin "15") (pinfunction "R-EXT_15") (pintype "passive"))
    )
    (net (code "76") (name "Net-(U1-SDO)") (class "Default")
      (node (ref "U1") (pin "14") (pinfunction "SDO_14") (pintype "passive"))
      (node (ref "U2") (pin "2") (pinfunction "SDI_2") (pintype "passive"))
    )
    (net (code "77") (name "Net-(U2-R-EXT)") (class "Default")
      (node (ref "R2") (pin "1") (pinfunction "1_1") (pintype "passive"))
      (node (ref "U2") (pin "15") (pinfunction "R-EXT_15") (pintype "passive"))
    )
    (net (code "78") (name "Net-(U2-SDO)") (class "Default")
      (node (ref "U2") (pin "14") (pinfunction "SDO_14") (pintype "passive"))
      (node (ref "U3") (pin "2") (pinfunction "SDI_2") (pintype "passive"))
    )
    (net (code "79") (name "Net-(U3-R-EXT)") (class "Default")
      (node (ref "R3") (pin "1") (pinfunction "1_1") (pintype "passive"))
      (node (ref "U3") (pin "15") (pinfunction "R-EXT_15") (pintype "passive"))
    )
    (net (code "80") (name "Net-(U3-SDO)") (class "Default")
      (node (ref "U3") (pin "14") (pinfunction "SDO_14") (pintype "passive"))
      (node (ref "U4") (pin "2") (pinfunction "SDI_2") (pintype "passive"))
    )
    (net (code "81") (name "Net-(U4-R-EXT)") (class "Default")
      (node (ref "R4") (pin "1") (pinfunction "1_1") (pintype "passive"))
      (node (ref "U4") (pin "15") (pinfunction "R-EXT_15") (pintype "passive"))
    )
    (net (code "82") (name "Net-(U4-SDO)") (class "Default")
      (node (ref "U4") (pin "14") (pinfunction "SDO_14") (pintype "passive"))
      (node (ref "U5") (pin "2") (pinfunction "SDI_2") (pintype "passive"))
    )
    (net (code "83") (name "Net-(U5-R-EXT)") (class "Default")
      (node (ref "R5") (pin "1") (pinfunction "1_1") (pintype "passive"))
      (node (ref "U5") (pin "15") (pinfunction "R-EXT_15") (pintype "passive"))
    )
    (net (code "84") (name "Net-(U5-SDO)") (class "Default")
      (node (ref "U5") (pin "14") (pinfunction "SDO_14") (pintype "passive"))
      (node (ref "U6") (pin "2") (pinfunction "SDI_2") (pintype "passive"))
    )
    (net (code "85") (name "Net-(U6-R-EXT)") (class "Default")
      (node (ref "R6") (pin "1") (pinfunction "1_1") (pintype "passive"))
      (node (ref "U6") (pin "15") (pinfunction "R-EXT_15") (pintype "passive"))
    )
    (net (code "86") (name "Net-(U6-SDO)") (class "Default")
      (node (ref "U6") (pin "14") (pinfunction "SDO_14") (pintype "passive"))
      (node (ref "U7") (pin "2") (pinfunction "SDI_2") (pintype "passive"))
    )
    (net (code "87") (name "Net-(U7-R-EXT)") (class "Default")
      (node (ref "R7") (pin "1") (pinfunction "1_1") (pintype "passive"))
      (node (ref "U7") (pin "15") (pinfunction "R-EXT_15") (pintype "passive"))
    )
    (net (code "88") (name "Net-(U7-SDO)") (class "Default")
      (node (ref "U7") (pin "14") (pinfunction "SDO_14") (pintype "passive"))
      (node (ref "U8") (pin "2") (pinfunction "SDI_2") (pintype "passive"))
    )
    (net (code "89") (name "Net-(U8-R-EXT)") (class "Default")
      (node (ref "R8") (pin "1") (pinfunction "1_1") (pintype "passive"))
      (node (ref "U8") (pin "15") (pinfunction "R-EXT_15") (pintype "passive"))
    )
    (net (code "90") (name "VCC") (class "Default")
      (node (ref "C1") (pin "2") (pinfunction "2_2") (pintype "passive"))
      (node (ref "C2") (pin "2") (pinfunction "2_2") (pintype "passive"))
      (node (ref "C3") (pin "2") (pinfunction "2_2") (pintype "passive"))
      (node (ref "C4") (pin "2") (pinfunction "2_2") (pintype "passive"))
      (node (ref "C5") (pin "2") (pinfunction "2_2") (pintype "passive"))
      (node (ref "C6") (pin "2") (pinfunction "2_2") (pintype "passive"))
      (node (ref "C7") (pin "2") (pinfunction "2_2") (pintype "passive"))
      (node (ref "C8") (pin "2") (pinfunction "2_2") (pintype "passive"))
      (node (ref "C9") (pin "2") (pinfunction "2_2") (pintype "passive"))
      (node (ref "J9") (pin "1") (pinfunction "1_1") (pintype "passive"))
      (node (ref "J9") (pin "2") (pinfunction "2_2") (pintype "passive"))
      (node (ref "U1") (pin "16") (pinfunction "VDD_16") (pintype "passive"))
      (node (ref "U2") (pin "16") (pinfunction "VDD_16") (pintype "passive"))
      (node (ref "U3") (pin "16") (pinfunction "VDD_16") (pintype "passive"))
      (node (ref "U4") (pin "16") (pinfunction "VDD_16") (pintype "passive"))
      (node (ref "U5") (pin "16") (pinfunction "VDD_16") (pintype "passive"))
      (node (ref "U6") (pin "16") (pinfunction "VDD_16") (pintype "passive"))
      (node (ref "U7") (pin "16") (pinfunction "VDD_16") (pintype "passive"))
      (node (ref "U8") (pin "16") (pinfunction "VDD_16") (pintype "passive"))
    )
  )
)
